# MCU089A_XDS110_MCU.net
KiCad netlist of a schematic drawn in Altium Designer
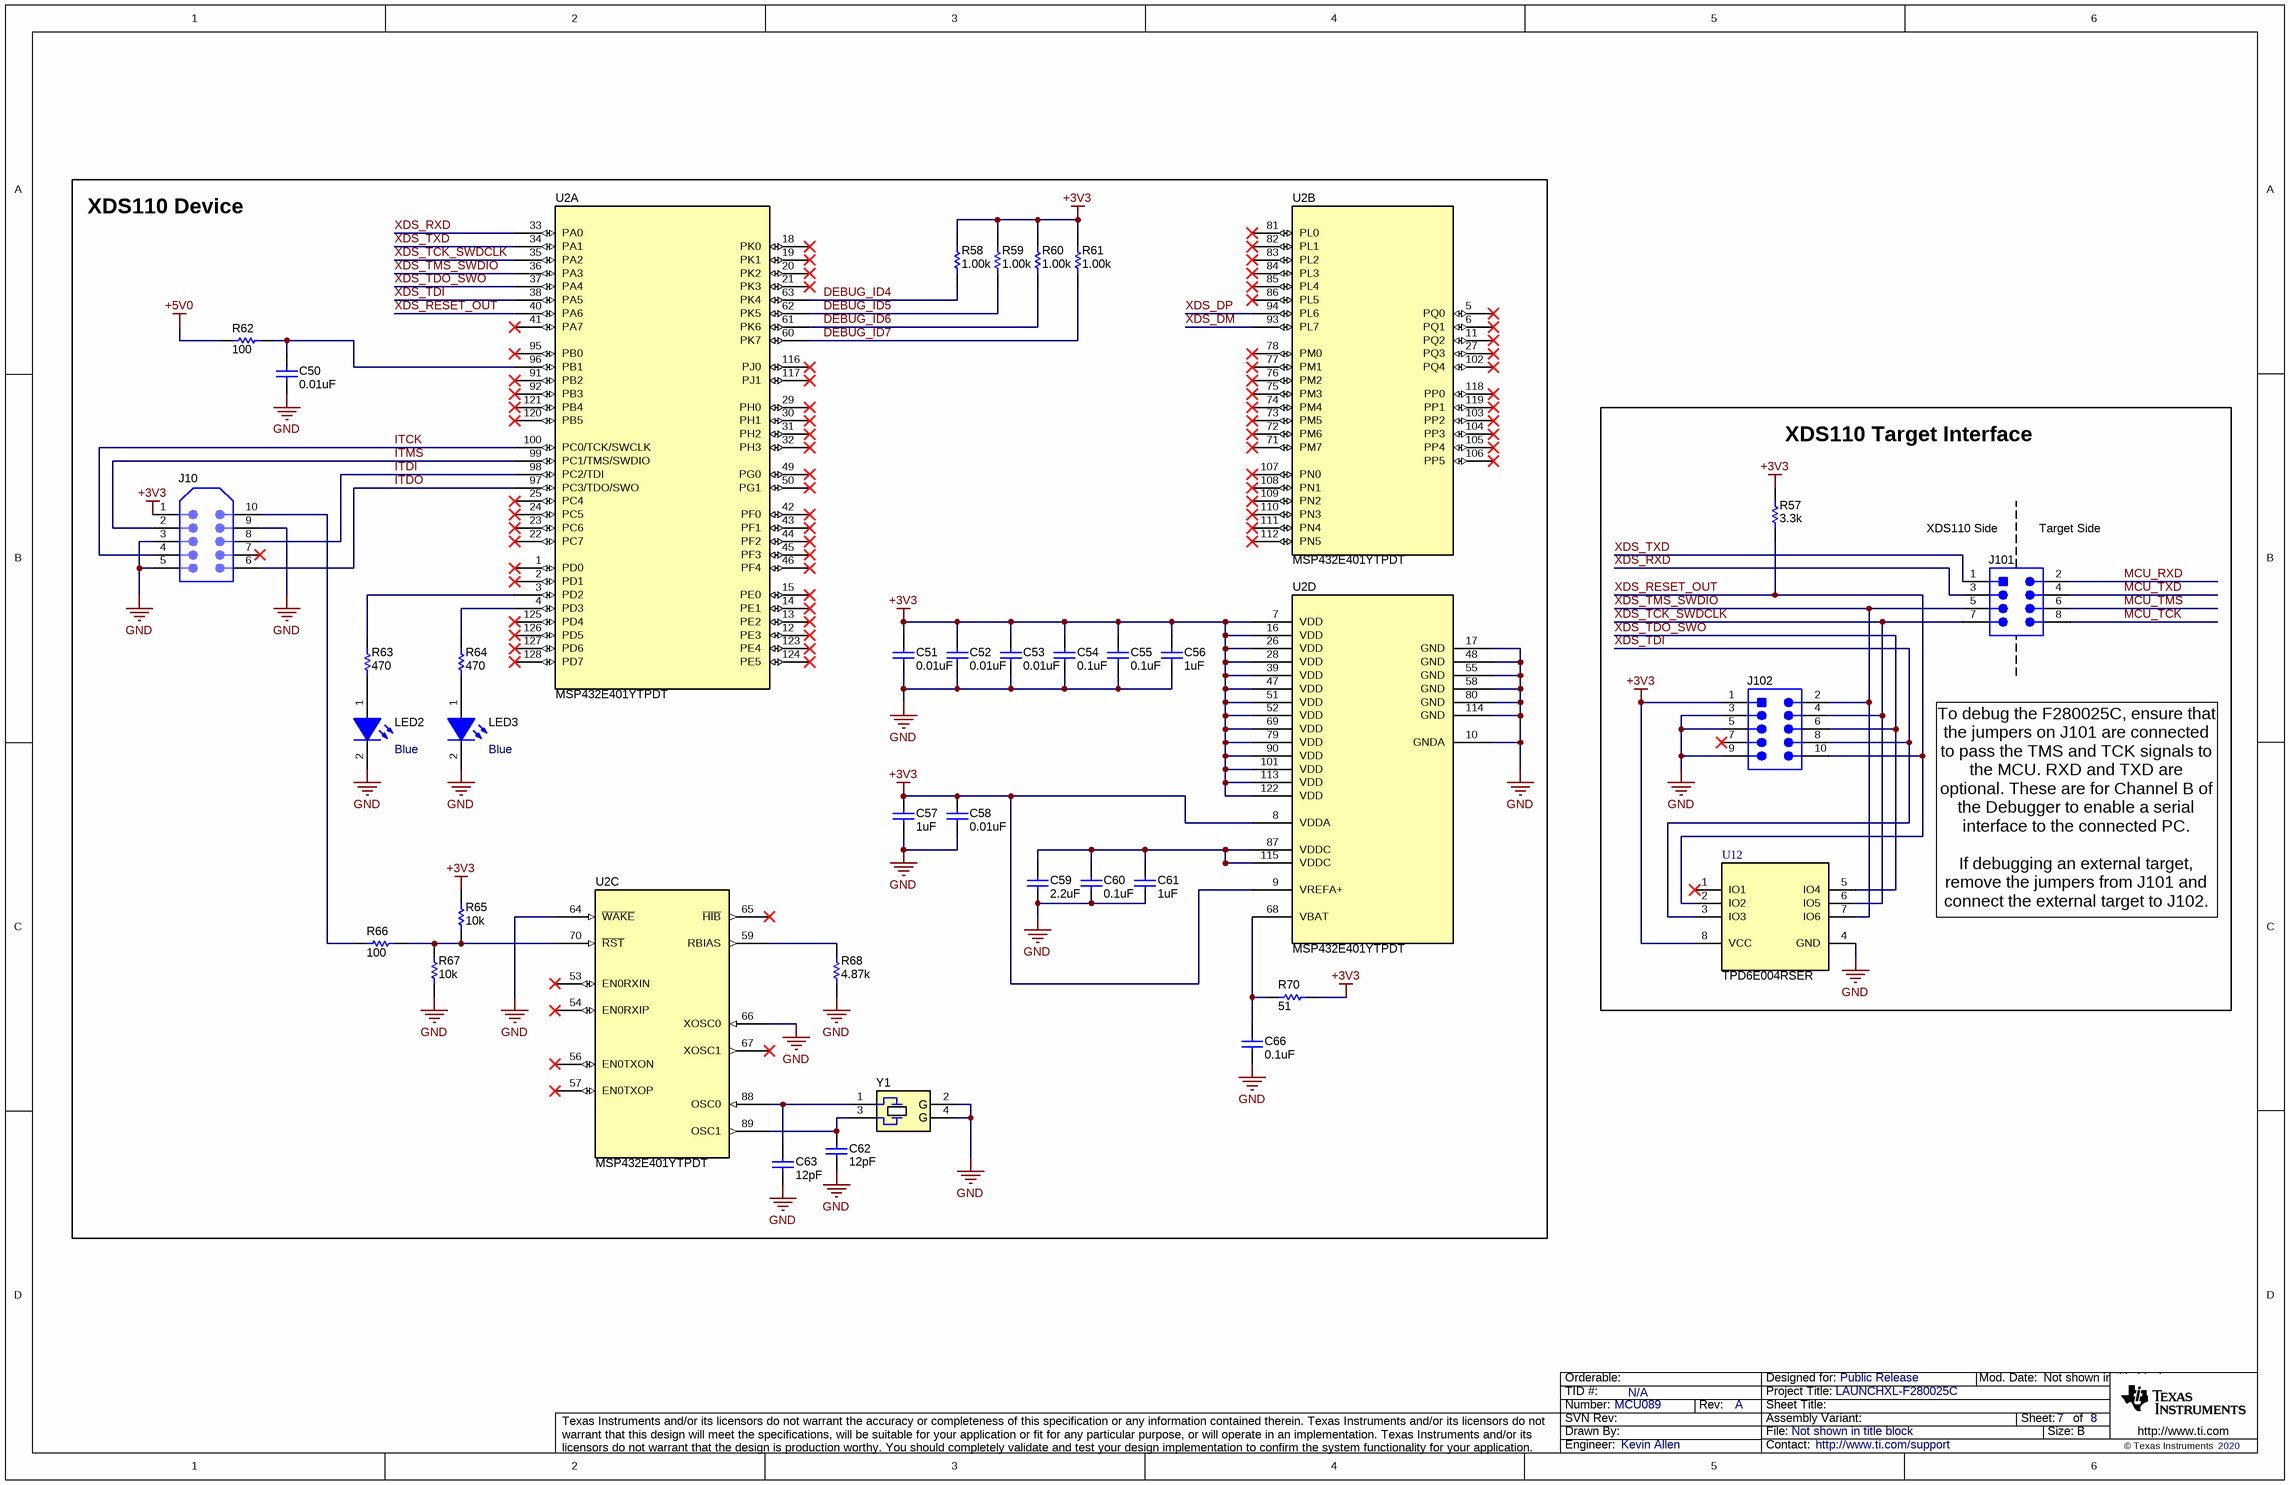
[diagram p0: MCU089A_XDS110_MCU.SchDoc]

(export (version "E")
  (design (tool "Eeschema 10.0.6"))
  (components
    (comp (ref "C50")
      (value "GRM155R71E103KA01D")
      (footprint "0402")
      (description "CAP, CERM, 0.01 uF, 25 V, +/- 10%, X7R, 0402")
      (fields
        (field (name "VALUEDISPLAYED") "0.01uF")
        (field (name "MANUFACTURER") "MuRata")
        (field (name "PUBLISHER") "Texas Instruments")
      )
      (libsource (lib "Altium Vault - TI") (part "Capacitor"))
    )
    (comp (ref "C51")
      (value "GRM155R71E103KA01D")
      (footprint "0402")
      (description "CAP, CERM, 0.01 uF, 25 V, +/- 10%, X7R, 0402")
      (fields
        (field (name "VALUEDISPLAYED") "0.01uF")
        (field (name "MANUFACTURER") "MuRata")
        (field (name "PUBLISHER") "Texas Instruments")
      )
      (libsource (lib "Altium Vault - TI") (part "Capacitor"))
    )
    (comp (ref "C52")
      (value "GRM155R71E103KA01D")
      (footprint "0402")
      (description "CAP, CERM, 0.01 uF, 25 V, +/- 10%, X7R, 0402")
      (fields
        (field (name "VALUEDISPLAYED") "0.01uF")
        (field (name "MANUFACTURER") "MuRata")
        (field (name "PUBLISHER") "Texas Instruments")
      )
      (libsource (lib "Altium Vault - TI") (part "Capacitor"))
    )
    (comp (ref "C53")
      (value "GRM155R71E103KA01D")
      (footprint "0402")
      (description "CAP, CERM, 0.01 uF, 25 V, +/- 10%, X7R, 0402")
      (fields
        (field (name "VALUEDISPLAYED") "0.01uF")
        (field (name "MANUFACTURER") "MuRata")
        (field (name "PUBLISHER") "Texas Instruments")
      )
      (libsource (lib "Altium Vault - TI") (part "Capacitor"))
    )
    (comp (ref "C54")
      (value "GRM155R70J104KA01D")
      (footprint "0402")
      (description "CAP, CERM, 0.1 uF, 6.3 V, +/- 10%, X7R, 0402")
      (fields
        (field (name "VALUEDISPLAYED") "0.1uF")
        (field (name "MANUFACTURER") "MuRata")
        (field (name "PUBLISHER") "Texas Instruments")
      )
      (libsource (lib "Altium Vault - TI") (part "Capacitor"))
    )
    (comp (ref "C55")
      (value "GRM155R70J104KA01D")
      (footprint "0402")
      (description "CAP, CERM, 0.1 uF, 6.3 V, +/- 10%, X7R, 0402")
      (fields
        (field (name "VALUEDISPLAYED") "0.1uF")
        (field (name "MANUFACTURER") "MuRata")
        (field (name "PUBLISHER") "Texas Instruments")
      )
      (libsource (lib "Altium Vault - TI") (part "Capacitor"))
    )
    (comp (ref "C56")
      (value "885012105012")
      (footprint "0402")
      (description "CAP, CERM, 1 uF, 10 V,+/- 20%, X5R, 0402")
      (fields
        (field (name "VALUEDISPLAYED") "1uF")
        (field (name "MANUFACTURER") "Wurth Elektronik")
        (field (name "PUBLISHER") "Texas Instruments")
      )
      (libsource (lib "Altium Vault - TI") (part "Capacitor"))
    )
    (comp (ref "C57")
      (value "885012105012")
      (footprint "0402")
      (description "CAP, CERM, 1 uF, 10 V,+/- 20%, X5R, 0402")
      (fields
        (field (name "VALUEDISPLAYED") "1uF")
        (field (name "MANUFACTURER") "Wurth Elektronik")
        (field (name "PUBLISHER") "Texas Instruments")
      )
      (libsource (lib "Altium Vault - TI") (part "Capacitor"))
    )
    (comp (ref "C58")
      (value "GRM155R71E103KA01D")
      (footprint "0402")
      (description "CAP, CERM, 0.01 uF, 25 V, +/- 10%, X7R, 0402")
      (fields
        (field (name "VALUEDISPLAYED") "0.01uF")
        (field (name "MANUFACTURER") "MuRata")
        (field (name "PUBLISHER") "Texas Instruments")
      )
      (libsource (lib "Altium Vault - TI") (part "Capacitor"))
    )
    (comp (ref "C59")
      (value "GRM155R60J225KE95D")
      (footprint "0402")
      (description "CAP, CERM, 2.2 uF, 6.3 V, +/- 10%, X5R, 0402")
      (fields
        (field (name "VALUEDISPLAYED") "2.2uF")
        (field (name "MANUFACTURER") "MuRata")
        (field (name "PUBLISHER") "Texas Instruments")
      )
      (libsource (lib "Altium Vault - TI") (part "Capacitor"))
    )
    (comp (ref "C60")
      (value "GRM155R70J104KA01D")
      (footprint "0402")
      (description "CAP, CERM, 0.1 uF, 6.3 V, +/- 10%, X7R, 0402")
      (fields
        (field (name "VALUEDISPLAYED") "0.1uF")
        (field (name "MANUFACTURER") "MuRata")
        (field (name "PUBLISHER") "Texas Instruments")
      )
      (libsource (lib "Altium Vault - TI") (part "Capacitor"))
    )
    (comp (ref "C61")
      (value "885012105012")
      (footprint "0402")
      (description "CAP, CERM, 1 uF, 10 V,+/- 20%, X5R, 0402")
      (fields
        (field (name "VALUEDISPLAYED") "1uF")
        (field (name "MANUFACTURER") "Wurth Elektronik")
        (field (name "PUBLISHER") "Texas Instruments")
      )
      (libsource (lib "Altium Vault - TI") (part "Capacitor"))
    )
    (comp (ref "C62")
      (value "C0402C120J3GACAUTO")
      (footprint "0402")
      (description "CAP, CERM, 12 pF, 25 V, +/- 5%, C0G/NP0, AEC-Q200 Grade 1, 0402")
      (fields
        (field (name "MANUFACTURER") "Kemet")
        (field (name "VALUEDISPLAYED") "12pF")
        (field (name "PUBLISHER") "Texas Instruments")
      )
      (libsource (lib "Altium Vault - TI") (part "Capacitor"))
    )
    (comp (ref "C63")
      (value "C0402C120J3GACAUTO")
      (footprint "0402")
      (description "CAP, CERM, 12 pF, 25 V, +/- 5%, C0G/NP0, AEC-Q200 Grade 1, 0402")
      (fields
        (field (name "MANUFACTURER") "Kemet")
        (field (name "VALUEDISPLAYED") "12pF")
        (field (name "PUBLISHER") "Texas Instruments")
      )
      (libsource (lib "Altium Vault - TI") (part "Capacitor"))
    )
    (comp (ref "C66")
      (value "GRM155R70J104KA01D")
      (footprint "0402")
      (description "CAP, CERM, 0.1 uF, 6.3 V, +/- 10%, X7R, 0402")
      (fields
        (field (name "VALUEDISPLAYED") "0.1uF")
        (field (name "MANUFACTURER") "MuRata")
        (field (name "PUBLISHER") "Texas Instruments")
      )
      (libsource (lib "Altium Vault - TI") (part "Capacitor"))
    )
    (comp (ref "J10")
      (value "TC2050-IDC-NL-FP")
      (footprint "Tag_TC2050-NL")
      (description "Footprint for Tag-Connect TC2050 No-Legs cables")
      (fields (field (name "MANUFACTURER") "Tag-Connect") (field (name "PUBLISHER") "Texas Instruments"))
      (libsource (lib "Altium Vault - TI") (part "CMP-0075101-1"))
    )
    (comp (ref "J101")
      (value "TSW-104-07-G-D")
      (footprint "TSW-104-07-G-D")
      (description "Header, 100mil, 4x2, Gold, TH")
      (fields (field (name "MANUFACTURER") "Samtec"))
      (libsource (lib "Altium Vault - TI") (part "Header_4x2"))
    )
    (comp (ref "J102")
      (value "FTSH-105-01-F-DV-K")
      (footprint "Samtec_FTSH-105-01-x-DV-K")
      (description "Header (Shrouded), 1.27mm, 5x2, Gold, SMT")
      (fields (field (name "MANUFACTURER") "Samtec"))
      (libsource (lib "Altium Vault - TI") (part "Header_5x2"))
    )
    (comp (ref "LED2")
      (value "Blue")
      (footprint "LTST-C170TBKT_Blue")
      (description "LED, Blue, SMD")
      (fields (field (name "PARTNUMBER") "LTST-C170TBKT") (field (name "MANUFACTURER") "Lite-On"))
      (libsource (lib "Altium Vault - TI") (part "LED"))
    )
    (comp (ref "LED3")
      (value "Blue")
      (footprint "LTST-C170TBKT_Blue")
      (description "LED, Blue, SMD")
      (fields (field (name "PARTNUMBER") "LTST-C170TBKT") (field (name "MANUFACTURER") "Lite-On"))
      (libsource (lib "Altium Vault - TI") (part "LED"))
    )
    (comp (ref "R57")
      (value "CRCW04023K30JNED")
      (footprint "0402")
      (description "RES, 3.3 k, 5%, 0.063 W, AEC-Q200 Grade 0, 0402")
      (fields (field (name "VALUEDISPLAYED") "3.3k") (field (name "MANUFACTURER") "Vishay-Dale"))
      (libsource (lib "Altium Vault - TI") (part "Resistor"))
    )
    (comp (ref "R58")
      (value "CRCW04021K00FKED")
      (footprint "0402")
      (description "RES, 1.00 k, 1%, 0.063 W, AEC-Q200 Grade 0, 0402")
      (fields (field (name "MANUFACTURER") "Vishay-Dale") (field (name "VALUEDISPLAYED") "1.00k"))
      (libsource (lib "Altium Vault - TI") (part "Resistor"))
    )
    (comp (ref "R59")
      (value "CRCW04021K00FKED")
      (footprint "0402")
      (description "RES, 1.00 k, 1%, 0.063 W, AEC-Q200 Grade 0, 0402")
      (fields (field (name "MANUFACTURER") "Vishay-Dale") (field (name "VALUEDISPLAYED") "1.00k"))
      (libsource (lib "Altium Vault - TI") (part "Resistor"))
    )
    (comp (ref "R60")
      (value "CRCW04021K00FKED")
      (footprint "0402")
      (description "RES, 1.00 k, 1%, 0.063 W, AEC-Q200 Grade 0, 0402")
      (fields (field (name "MANUFACTURER") "Vishay-Dale") (field (name "VALUEDISPLAYED") "1.00k"))
      (libsource (lib "Altium Vault - TI") (part "Resistor"))
    )
    (comp (ref "R61")
      (value "CRCW04021K00FKED")
      (footprint "0402")
      (description "RES, 1.00 k, 1%, 0.063 W, AEC-Q200 Grade 0, 0402")
      (fields (field (name "MANUFACTURER") "Vishay-Dale") (field (name "VALUEDISPLAYED") "1.00k"))
      (libsource (lib "Altium Vault - TI") (part "Resistor"))
    )
    (comp (ref "R62")
      (value "CRCW0402100RJNED")
      (footprint "0402")
      (description "RES, 100, 5%, 0.063 W, AEC-Q200 Grade 0, 0402")
      (fields (field (name "VALUEDISPLAYED") "100") (field (name "MANUFACTURER") "Vishay-Dale"))
      (libsource (lib "Altium Vault - TI") (part "Resistor"))
    )
    (comp (ref "R63")
      (value "ERJ-2RKF4700X")
      (footprint "0402")
      (description "RES, 470, 1%, 0.1 W, AEC-Q200 Grade 0, 0402")
      (fields
        (field (name "VALUEDISPLAYED") "470")
        (field (name "MANUFACTURER") "Panasonic")
        (field (name "PUBLISHER") "Texas Instruments")
      )
      (libsource (lib "Altium Vault - TI") (part "Resistor"))
    )
    (comp (ref "R64")
      (value "ERJ-2RKF4700X")
      (footprint "0402")
      (description "RES, 470, 1%, 0.1 W, AEC-Q200 Grade 0, 0402")
      (fields
        (field (name "VALUEDISPLAYED") "470")
        (field (name "MANUFACTURER") "Panasonic")
        (field (name "PUBLISHER") "Texas Instruments")
      )
      (libsource (lib "Altium Vault - TI") (part "Resistor"))
    )
    (comp (ref "R65")
      (value "CRCW040210K0JNED")
      (footprint "0402")
      (description "RES, 10 k, 5%, 0.063 W, AEC-Q200 Grade 0, 0402")
      (fields (field (name "VALUEDISPLAYED") "10k") (field (name "MANUFACTURER") "Vishay-Dale"))
      (libsource (lib "Altium Vault - TI") (part "Resistor"))
    )
    (comp (ref "R66")
      (value "CRCW0402100RJNED")
      (footprint "0402")
      (description "RES, 100, 5%, 0.063 W, AEC-Q200 Grade 0, 0402")
      (fields (field (name "VALUEDISPLAYED") "100") (field (name "MANUFACTURER") "Vishay-Dale"))
      (libsource (lib "Altium Vault - TI") (part "Resistor"))
    )
    (comp (ref "R67")
      (value "CRCW040210K0JNED")
      (footprint "0402")
      (description "RES, 10 k, 5%, 0.063 W, AEC-Q200 Grade 0, 0402")
      (fields (field (name "VALUEDISPLAYED") "10k") (field (name "MANUFACTURER") "Vishay-Dale"))
      (libsource (lib "Altium Vault - TI") (part "Resistor"))
    )
    (comp (ref "R68")
      (value "CRCW04024K87FKED")
      (footprint "0402")
      (description "RES, 4.87 k, 1%, 0.063 W, AEC-Q200 Grade 0, 0402")
      (fields (field (name "VALUEDISPLAYED") "4.87k") (field (name "MANUFACTURER") "Vishay-Dale"))
      (libsource (lib "Altium Vault - TI") (part "Resistor"))
    )
    (comp (ref "R70")
      (value "CRCW040251R0JNED")
      (footprint "0402")
      (description "RES, 51, 5%, 0.063 W, AEC-Q200 Grade 0, 0402")
      (fields (field (name "VALUEDISPLAYED") "51") (field (name "MANUFACTURER") "Vishay-Dale"))
      (libsource (lib "Altium Vault - TI") (part "Resistor"))
    )
    (comp (ref "U2")
      (value "MSP432E401YTPDT")
      (footprint "PDT0128A")
      (description "MSP432E401YTPDT, PDT0128A (TQFP-128)")
      (fields
        (field (name "ALTERNATE PARTNUMBER") "MSP432E401YTPDTR")
        (field (name "MANUFACTURER") "Texas Instruments")
        (field (name "PARTNUMBER") "MSP432E401YTPDT")
      )
      (libsource (lib "Altium Vault - TI") (part "MSP432E401YTPDT"))
    )
    (comp (ref "U12")
      (value "TPD6E004RSER")
      (footprint "RSE0008A")
      (fields (field (name "MANUFACTURER") "Texas Instruments") (field (name "PARTNUMBER") "TPD6E004RSER"))
      (libsource (lib "Altium Vault - TI") (part "TI-TPD6E004-UQFN_RSE-8"))
    )
    (comp (ref "Y1")
      (value "NX3225GA-16.000M-STD-CRG-1")
      (footprint "NDK_NX3225GA")
      (description "Crystal, 16 MHz, 8pF, SMD")
      (fields (field (name "MANUFACTURER") "NDK"))
      (libsource (lib "Altium Vault - TI") (part "XTAL_4P_13_G24"))
    )
  )
  (nets
    (net (code "1") (name "+3V3") (class "Default")
      (node (ref "C51") (pin "1") (pinfunction "1_1") (pintype "passive"))
      (node (ref "C52") (pin "1") (pinfunction "1_1") (pintype "passive"))
      (node (ref "C53") (pin "1") (pinfunction "1_1") (pintype "passive"))
      (node (ref "C54") (pin "1") (pinfunction "1_1") (pintype "passive"))
      (node (ref "C55") (pin "1") (pinfunction "1_1") (pintype "passive"))
      (node (ref "C56") (pin "1") (pinfunction "1_1") (pintype "passive"))
      (node (ref "C57") (pin "1") (pinfunction "1_1") (pintype "passive"))
      (node (ref "C58") (pin "1") (pinfunction "1_1") (pintype "passive"))
      (node (ref "J10") (pin "1") (pinfunction "1_1") (pintype "passive"))
      (node (ref "J102") (pin "1") (pinfunction "1_1") (pintype "passive"))
      (node (ref "R57") (pin "2") (pinfunction "2_2") (pintype "passive"))
      (node (ref "R58") (pin "2") (pinfunction "2_2") (pintype "passive"))
      (node (ref "R59") (pin "2") (pinfunction "2_2") (pintype "passive"))
      (node (ref "R60") (pin "2") (pinfunction "2_2") (pintype "passive"))
      (node (ref "R61") (pin "2") (pinfunction "2_2") (pintype "passive"))
      (node (ref "R65") (pin "2") (pinfunction "2_2") (pintype "passive"))
      (node (ref "R70") (pin "2") (pinfunction "2_2") (pintype "passive"))
      (node (ref "U12") (pin "8") (pinfunction "VCC_8") (pintype "power_in"))
      (node (ref "U2") (pin "101") (pinfunction "VDD_101") (pintype "power_in"))
      (node (ref "U2") (pin "113") (pinfunction "VDD_113") (pintype "power_in"))
      (node (ref "U2") (pin "122") (pinfunction "VDD_122") (pintype "power_in"))
      (node (ref "U2") (pin "16") (pinfunction "VDD_16") (pintype "power_in"))
      (node (ref "U2") (pin "26") (pinfunction "VDD_26") (pintype "power_in"))
      (node (ref "U2") (pin "28") (pinfunction "VDD_28") (pintype "power_in"))
      (node (ref "U2") (pin "39") (pinfunction "VDD_39") (pintype "power_in"))
      (node (ref "U2") (pin "47") (pinfunction "VDD_47") (pintype "power_in"))
      (node (ref "U2") (pin "51") (pinfunction "VDD_51") (pintype "power_in"))
      (node (ref "U2") (pin "52") (pinfunction "VDD_52") (pintype "power_in"))
      (node (ref "U2") (pin "69") (pinfunction "VDD_69") (pintype "power_in"))
      (node (ref "U2") (pin "7") (pinfunction "VDD_7") (pintype "power_in"))
      (node (ref "U2") (pin "79") (pinfunction "VDD_79") (pintype "power_in"))
      (node (ref "U2") (pin "8") (pinfunction "VDDA_8") (pintype "power_in"))
      (node (ref "U2") (pin "9") (pinfunction "VREFA+_9") (pintype "power_in"))
      (node (ref "U2") (pin "90") (pinfunction "VDD_90") (pintype "power_in"))
    )
    (net (code "2") (name "+5V0") (class "Default")
      (node (ref "R62") (pin "1") (pinfunction "1_1") (pintype "passive"))
    )
    (net (code "3") (name "/DEBUG_ID4") (class "Default")
      (node (ref "R58") (pin "1") (pinfunction "1_1") (pintype "passive"))
      (node (ref "U2") (pin "63") (pinfunction "PK4_63") (pintype "bidirectional"))
    )
    (net (code "4") (name "/DEBUG_ID5") (class "Default")
      (node (ref "R59") (pin "1") (pinfunction "1_1") (pintype "passive"))
      (node (ref "U2") (pin "62") (pinfunction "PK5_62") (pintype "bidirectional"))
    )
    (net (code "5") (name "/DEBUG_ID6") (class "Default")
      (node (ref "R60") (pin "1") (pinfunction "1_1") (pintype "passive"))
      (node (ref "U2") (pin "61") (pinfunction "PK6_61") (pintype "bidirectional"))
    )
    (net (code "6") (name "/DEBUG_ID7") (class "Default")
      (node (ref "R61") (pin "1") (pinfunction "1_1") (pintype "passive"))
      (node (ref "U2") (pin "60") (pinfunction "PK7_60") (pintype "bidirectional"))
    )
    (net (code "7") (name "/ITCK") (class "Default")
      (node (ref "J10") (pin "4") (pinfunction "4_4") (pintype "passive"))
      (node (ref "U2") (pin "100") (pinfunction "PC0/TCK/SWCLK_100") (pintype "bidirectional"))
    )
    (net (code "8") (name "/ITDI") (class "Default")
      (node (ref "J10") (pin "8") (pinfunction "8_8") (pintype "passive"))
      (node (ref "U2") (pin "98") (pinfunction "PC2/TDI_98") (pintype "bidirectional"))
    )
    (net (code "9") (name "/ITDO") (class "Default")
      (node (ref "J10") (pin "6") (pinfunction "6_6") (pintype "passive"))
      (node (ref "U2") (pin "97") (pinfunction "PC3/TDO/SWO_97") (pintype "bidirectional"))
    )
    (net (code "10") (name "/ITMS") (class "Default")
      (node (ref "J10") (pin "2") (pinfunction "2_2") (pintype "passive"))
      (node (ref "U2") (pin "99") (pinfunction "PC1/TMS/SWDIO_99") (pintype "bidirectional"))
    )
    (net (code "11") (name "/MCU_RXD") (class "Default")
      (node (ref "J101") (pin "2") (pinfunction "2_2") (pintype "passive"))
    )
    (net (code "12") (name "/MCU_TCK") (class "Default")
      (node (ref "J101") (pin "8") (pinfunction "8_8") (pintype "passive"))
    )
    (net (code "13") (name "/MCU_TMS") (class "Default")
      (node (ref "J101") (pin "6") (pinfunction "6_6") (pintype "passive"))
    )
    (net (code "14") (name "/MCU_TXD") (class "Default")
      (node (ref "J101") (pin "4") (pinfunction "4_4") (pintype "passive"))
    )
    (net (code "15") (name "/XDS_DM") (class "Default")
      (node (ref "U2") (pin "93") (pinfunction "PL7_93") (pintype "bidirectional"))
    )
    (net (code "16") (name "/XDS_DP") (class "Default")
      (node (ref "U2") (pin "94") (pinfunction "PL6_94") (pintype "bidirectional"))
    )
    (net (code "17") (name "/XDS_RESET_OUT") (class "Default")
      (node (ref "J102") (pin "10") (pinfunction "10_10") (pintype "passive"))
      (node (ref "R57") (pin "1") (pinfunction "1_1") (pintype "passive"))
      (node (ref "U12") (pin "2") (pinfunction "IO2_2") (pintype "passive"))
      (node (ref "U2") (pin "40") (pinfunction "PA6_40") (pintype "bidirectional"))
    )
    (net (code "18") (name "/XDS_RXD") (class "Default")
      (node (ref "J101") (pin "3") (pinfunction "3_3") (pintype "passive"))
      (node (ref "U2") (pin "33") (pinfunction "PA0_33") (pintype "bidirectional"))
    )
    (net (code "19") (name "/XDS_TCK_SWDCLK") (class "Default")
      (node (ref "J101") (pin "7") (pinfunction "7_7") (pintype "passive"))
      (node (ref "J102") (pin "4") (pinfunction "4_4") (pintype "passive"))
      (node (ref "U12") (pin "6") (pinfunction "IO5_6") (pintype "passive"))
      (node (ref "U2") (pin "35") (pinfunction "PA2_35") (pintype "bidirectional"))
    )
    (net (code "20") (name "/XDS_TDI") (class "Default")
      (node (ref "J102") (pin "8") (pinfunction "8_8") (pintype "passive"))
      (node (ref "U12") (pin "3") (pinfunction "IO3_3") (pintype "passive"))
      (node (ref "U2") (pin "38") (pinfunction "PA5_38") (pintype "bidirectional"))
    )
    (net (code "21") (name "/XDS_TDO_SWO") (class "Default")
      (node (ref "J102") (pin "6") (pinfunction "6_6") (pintype "passive"))
      (node (ref "U12") (pin "5") (pinfunction "IO4_5") (pintype "passive"))
      (node (ref "U2") (pin "37") (pinfunction "PA4_37") (pintype "bidirectional"))
    )
    (net (code "22") (name "/XDS_TMS_SWDIO") (class "Default")
      (node (ref "J101") (pin "5") (pinfunction "5_5") (pintype "passive"))
      (node (ref "J102") (pin "2") (pinfunction "2_2") (pintype "passive"))
      (node (ref "U12") (pin "7") (pinfunction "IO6_7") (pintype "passive"))
      (node (ref "U2") (pin "36") (pinfunction "PA3_36") (pintype "bidirectional"))
    )
    (net (code "23") (name "/XDS_TXD") (class "Default")
      (node (ref "J101") (pin "1") (pinfunction "1_1") (pintype "passive"))
      (node (ref "U2") (pin "34") (pinfunction "PA1_34") (pintype "bidirectional"))
    )
    (net (code "24") (name "GND") (class "Default")
      (node (ref "C50") (pin "2") (pinfunction "2_2") (pintype "passive"))
      (node (ref "C51") (pin "2") (pinfunction "2_2") (pintype "passive"))
      (node (ref "C52") (pin "2") (pinfunction "2_2") (pintype "passive"))
      (node (ref "C53") (pin "2") (pinfunction "2_2") (pintype "passive"))
      (node (ref "C54") (pin "2") (pinfunction "2_2") (pintype "passive"))
      (node (ref "C55") (pin "2") (pinfunction "2_2") (pintype "passive"))
      (node (ref "C56") (pin "2") (pinfunction "2_2") (pintype "passive"))
      (node (ref "C57") (pin "2") (pinfunction "2_2") (pintype "passive"))
      (node (ref "C58") (pin "2") (pinfunction "2_2") (pintype "passive"))
      (node (ref "C59") (pin "2") (pinfunction "2_2") (pintype "passive"))
      (node (ref "C60") (pin "2") (pinfunction "2_2") (pintype "passive"))
      (node (ref "C61") (pin "2") (pinfunction "2_2") (pintype "passive"))
      (node (ref "C62") (pin "2") (pinfunction "2_2") (pintype "passive"))
      (node (ref "C63") (pin "2") (pinfunction "2_2") (pintype "passive"))
      (node (ref "C66") (pin "2") (pinfunction "2_2") (pintype "passive"))
      (node (ref "J10") (pin "3") (pinfunction "3_3") (pintype "passive"))
      (node (ref "J10") (pin "5") (pinfunction "5_5") (pintype "passive"))
      (node (ref "J10") (pin "9") (pinfunction "9_9") (pintype "passive"))
      (node (ref "J102") (pin "3") (pinfunction "3_3") (pintype "passive"))
      (node (ref "J102") (pin "5") (pinfunction "5_5") (pintype "passive"))
      (node (ref "J102") (pin "9") (pinfunction "9_9") (pintype "passive"))
      (node (ref "LED2") (pin "2") (pinfunction "K_2") (pintype "passive"))
      (node (ref "LED3") (pin "2") (pinfunction "K_2") (pintype "passive"))
      (node (ref "R67") (pin "1") (pinfunction "1_1") (pintype "passive"))
      (node (ref "R68") (pin "1") (pinfunction "1_1") (pintype "passive"))
      (node (ref "U12") (pin "4") (pinfunction "GND_4") (pintype "power_in"))
      (node (ref "U2") (pin "10") (pinfunction "GNDA_10") (pintype "power_in"))
      (node (ref "U2") (pin "114") (pinfunction "GND_114") (pintype "power_in"))
      (node (ref "U2") (pin "17") (pinfunction "GND_17") (pintype "power_in"))
      (node (ref "U2") (pin "48") (pinfunction "GND_48") (pintype "power_in"))
      (node (ref "U2") (pin "55") (pinfunction "GND_55") (pintype "power_in"))
      (node (ref "U2") (pin "58") (pinfunction "GND_58") (pintype "power_in"))
      (node (ref "U2") (pin "64") (pinfunction "WAKE_64") (pintype "input"))
      (node (ref "U2") (pin "66") (pinfunction "XOSC0_66") (pintype "input"))
      (node (ref "U2") (pin "80") (pinfunction "GND_80") (pintype "power_in"))
      (node (ref "Y1") (pin "2") (pinfunction "GND_2") (pintype "power_in"))
      (node (ref "Y1") (pin "4") (pinfunction "GND_4") (pintype "power_in"))
    )
    (net (code "25") (name "Net-(C59-Pad1)") (class "Default")
      (node (ref "C59") (pin "1") (pinfunction "1_1") (pintype "passive"))
      (node (ref "C60") (pin "1") (pinfunction "1_1") (pintype "passive"))
      (node (ref "C61") (pin "1") (pinfunction "1_1") (pintype "passive"))
      (node (ref "U2") (pin "115") (pinfunction "VDDC_115") (pintype "power_in"))
      (node (ref "U2") (pin "87") (pinfunction "VDDC_87") (pintype "power_in"))
    )
    (net (code "26") (name "Net-(J10-Pad10)") (class "Default")
      (node (ref "J10") (pin "10") (pinfunction "10_10") (pintype "passive"))
      (node (ref "R66") (pin "1") (pinfunction "1_1") (pintype "passive"))
    )
    (net (code "27") (name "Net-(LED2-A)") (class "Default")
      (node (ref "LED2") (pin "1") (pinfunction "A_1") (pintype "passive"))
      (node (ref "R63") (pin "1") (pinfunction "1_1") (pintype "passive"))
    )
    (net (code "28") (name "Net-(LED3-A)") (class "Default")
      (node (ref "LED3") (pin "1") (pinfunction "A_1") (pintype "passive"))
      (node (ref "R64") (pin "1") (pinfunction "1_1") (pintype "passive"))
    )
    (net (code "29") (name "Net-(U2A-PB1)") (class "Default")
      (node (ref "C50") (pin "1") (pinfunction "1_1") (pintype "passive"))
      (node (ref "R62") (pin "2") (pinfunction "2_2") (pintype "passive"))
      (node (ref "U2") (pin "96") (pinfunction "PB1_96") (pintype "bidirectional"))
    )
    (net (code "30") (name "Net-(U2A-PD2)") (class "Default")
      (node (ref "R63") (pin "2") (pinfunction "2_2") (pintype "passive"))
      (node (ref "U2") (pin "3") (pinfunction "PD2_3") (pintype "bidirectional"))
    )
    (net (code "31") (name "Net-(U2A-PD3)") (class "Default")
      (node (ref "R64") (pin "2") (pinfunction "2_2") (pintype "passive"))
      (node (ref "U2") (pin "4") (pinfunction "PD3_4") (pintype "bidirectional"))
    )
    (net (code "32") (name "Net-(U2C-OSC0)") (class "Default")
      (node (ref "C63") (pin "1") (pinfunction "1_1") (pintype "passive"))
      (node (ref "U2") (pin "88") (pinfunction "OSC0_88") (pintype "input"))
      (node (ref "Y1") (pin "1") (pinfunction "1_1") (pintype "passive"))
    )
    (net (code "33") (name "Net-(U2C-OSC1)") (class "Default")
      (node (ref "C62") (pin "1") (pinfunction "1_1") (pintype "passive"))
      (node (ref "U2") (pin "89") (pinfunction "OSC1_89") (pintype "output"))
      (node (ref "Y1") (pin "3") (pinfunction "3_3") (pintype "passive"))
    )
    (net (code "34") (name "Net-(U2C-RBIAS)") (class "Default")
      (node (ref "R68") (pin "2") (pinfunction "2_2") (pintype "passive"))
      (node (ref "U2") (pin "59") (pinfunction "RBIAS_59") (pintype "output"))
    )
    (net (code "35") (name "Net-(U2C-RST)") (class "Default")
      (node (ref "R65") (pin "1") (pinfunction "1_1") (pintype "passive"))
      (node (ref "R66") (pin "2") (pinfunction "2_2") (pintype "passive"))
      (node (ref "R67") (pin "2") (pinfunction "2_2") (pintype "passive"))
      (node (ref "U2") (pin "70") (pinfunction "RST_70") (pintype "input"))
    )
    (net (code "36") (name "Net-(U2D-VBAT)") (class "Default")
      (node (ref "C66") (pin "1") (pinfunction "1_1") (pintype "passive"))
      (node (ref "R70") (pin "1") (pinfunction "1_1") (pintype "passive"))
      (node (ref "U2") (pin "68") (pinfunction "VBAT_68") (pintype "power_in"))
    )
    (net (code "37") (name "unconnected-(J10-Pad7)") (class "Default")
      (node (ref "J10") (pin "7") (pinfunction "7_7") (pintype "passive+no_connect"))
    )
    (net (code "38") (name "unconnected-(J102-Pad7)") (class "Default")
      (node (ref "J102") (pin "7") (pinfunction "7_7") (pintype "passive+no_connect"))
    )
    (net (code "39") (name "unconnected-(U2A-PA7-Pad41)") (class "Default")
      (node (ref "U2") (pin "41") (pinfunction "PA7_41") (pintype "bidirectional+no_connect"))
    )
    (net (code "40") (name "unconnected-(U2A-PB0-Pad95)") (class "Default")
      (node (ref "U2") (pin "95") (pinfunction "PB0_95") (pintype "bidirectional+no_connect"))
    )
    (net (code "41") (name "unconnected-(U2A-PB2-Pad91)") (class "Default")
      (node (ref "U2") (pin "91") (pinfunction "PB2_91") (pintype "bidirectional+no_connect"))
    )
    (net (code "42") (name "unconnected-(U2A-PB3-Pad92)") (class "Default")
      (node (ref "U2") (pin "92") (pinfunction "PB3_92") (pintype "bidirectional+no_connect"))
    )
    (net (code "43") (name "unconnected-(U2A-PB4-Pad121)") (class "Default")
      (node (ref "U2") (pin "121") (pinfunction "PB4_121") (pintype "bidirectional+no_connect"))
    )
    (net (code "44") (name "unconnected-(U2A-PB5-Pad120)") (class "Default")
      (node (ref "U2") (pin "120") (pinfunction "PB5_120") (pintype "bidirectional+no_connect"))
    )
    (net (code "45") (name "unconnected-(U2A-PC4-Pad25)") (class "Default")
      (node (ref "U2") (pin "25") (pinfunction "PC4_25") (pintype "bidirectional+no_connect"))
    )
    (net (code "46") (name "unconnected-(U2A-PC5-Pad24)") (class "Default")
      (node (ref "U2") (pin "24") (pinfunction "PC5_24") (pintype "bidirectional+no_connect"))
    )
    (net (code "47") (name "unconnected-(U2A-PC6-Pad23)") (class "Default")
      (node (ref "U2") (pin "23") (pinfunction "PC6_23") (pintype "bidirectional+no_connect"))
    )
    (net (code "48") (name "unconnected-(U2A-PC7-Pad22)") (class "Default")
      (node (ref "U2") (pin "22") (pinfunction "PC7_22") (pintype "bidirectional+no_connect"))
    )
    (net (code "49") (name "unconnected-(U2A-PD0-Pad1)") (class "Default")
      (node (ref "U2") (pin "1") (pinfunction "PD0_1") (pintype "bidirectional+no_connect"))
    )
    (net (code "50") (name "unconnected-(U2A-PD1-Pad2)") (class "Default")
      (node (ref "U2") (pin "2") (pinfunction "PD1_2") (pintype "bidirectional+no_connect"))
    )
    (net (code "51") (name "unconnected-(U2A-PD4-Pad125)") (class "Default")
      (node (ref "U2") (pin "125") (pinfunction "PD4_125") (pintype "bidirectional+no_connect"))
    )
    (net (code "52") (name "unconnected-(U2A-PD5-Pad126)") (class "Default")
      (node (ref "U2") (pin "126") (pinfunction "PD5_126") (pintype "bidirectional+no_connect"))
    )
    (net (code "53") (name "unconnected-(U2A-PD6-Pad127)") (class "Default")
      (node (ref "U2") (pin "127") (pinfunction "PD6_127") (pintype "bidirectional+no_connect"))
    )
    (net (code "54") (name "unconnected-(U2A-PD7-Pad128)") (class "Default")
      (node (ref "U2") (pin "128") (pinfunction "PD7_128") (pintype "bidirectional+no_connect"))
    )
    (net (code "55") (name "unconnected-(U2A-PE0-Pad15)") (class "Default")
      (node (ref "U2") (pin "15") (pinfunction "PE0_15") (pintype "bidirectional+no_connect"))
    )
    (net (code "56") (name "unconnected-(U2A-PE1-Pad14)") (class "Default")
      (node (ref "U2") (pin "14") (pinfunction "PE1_14") (pintype "bidirectional+no_connect"))
    )
    (net (code "57") (name "unconnected-(U2A-PE2-Pad13)") (class "Default")
      (node (ref "U2") (pin "13") (pinfunction "PE2_13") (pintype "bidirectional+no_connect"))
    )
    (net (code "58") (name "unconnected-(U2A-PE3-Pad12)") (class "Default")
      (node (ref "U2") (pin "12") (pinfunction "PE3_12") (pintype "bidirectional+no_connect"))
    )
    (net (code "59") (name "unconnected-(U2A-PE4-Pad123)") (class "Default")
      (node (ref "U2") (pin "123") (pinfunction "PE4_123") (pintype "bidirectional+no_connect"))
    )
    (net (code "60") (name "unconnected-(U2A-PE5-Pad124)") (class "Default")
      (node (ref "U2") (pin "124") (pinfunction "PE5_124") (pintype "bidirectional+no_connect"))
    )
    (net (code "61") (name "unconnected-(U2A-PF0-Pad42)") (class "Default")
      (node (ref "U2") (pin "42") (pinfunction "PF0_42") (pintype "bidirectional+no_connect"))
    )
    (net (code "62") (name "unconnected-(U2A-PF1-Pad43)") (class "Default")
      (node (ref "U2") (pin "43") (pinfunction "PF1_43") (pintype "bidirectional+no_connect"))
    )
    (net (code "63") (name "unconnected-(U2A-PF2-Pad44)") (class "Default")
      (node (ref "U2") (pin "44") (pinfunction "PF2_44") (pintype "bidirectional+no_connect"))
    )
    (net (code "64") (name "unconnected-(U2A-PF3-Pad45)") (class "Default")
      (node (ref "U2") (pin "45") (pinfunction "PF3_45") (pintype "bidirectional+no_connect"))
    )
    (net (code "65") (name "unconnected-(U2A-PF4-Pad46)") (class "Default")
      (node (ref "U2") (pin "46") (pinfunction "PF4_46") (pintype "bidirectional+no_connect"))
    )
    (net (code "66") (name "unconnected-(U2A-PG0-Pad49)") (class "Default")
      (node (ref "U2") (pin "49") (pinfunction "PG0_49") (pintype "bidirectional+no_connect"))
    )
    (net (code "67") (name "unconnected-(U2A-PG1-Pad50)") (class "Default")
      (node (ref "U2") (pin "50") (pinfunction "PG1_50") (pintype "bidirectional+no_connect"))
    )
    (net (code "68") (name "unconnected-(U2A-PH0-Pad29)") (class "Default")
      (node (ref "U2") (pin "29") (pinfunction "PH0_29") (pintype "bidirectional+no_connect"))
    )
    (net (code "69") (name "unconnected-(U2A-PH1-Pad30)") (class "Default")
      (node (ref "U2") (pin "30") (pinfunction "PH1_30") (pintype "bidirectional+no_connect"))
    )
    (net (code "70") (name "unconnected-(U2A-PH2-Pad31)") (class "Default")
      (node (ref "U2") (pin "31") (pinfunction "PH2_31") (pintype "bidirectional+no_connect"))
    )
    (net (code "71") (name "unconnected-(U2A-PH3-Pad32)") (class "Default")
      (node (ref "U2") (pin "32") (pinfunction "PH3_32") (pintype "bidirectional+no_connect"))
    )
    (net (code "72") (name "unconnected-(U2A-PJ0-Pad116)") (class "Default")
      (node (ref "U2") (pin "116") (pinfunction "PJ0_116") (pintype "bidirectional+no_connect"))
    )
    (net (code "73") (name "unconnected-(U2A-PJ1-Pad117)") (class "Default")
      (node (ref "U2") (pin "117") (pinfunction "PJ1_117") (pintype "bidirectional+no_connect"))
    )
    (net (code "74") (name "unconnected-(U2A-PK0-Pad18)") (class "Default")
      (node (ref "U2") (pin "18") (pinfunction "PK0_18") (pintype "bidirectional+no_connect"))
    )
    (net (code "75") (name "unconnected-(U2A-PK1-Pad19)") (class "Default")
      (node (ref "U2") (pin "19") (pinfunction "PK1_19") (pintype "bidirectional+no_connect"))
    )
    (net (code "76") (name "unconnected-(U2A-PK2-Pad20)") (class "Default")
      (node (ref "U2") (pin "20") (pinfunction "PK2_20") (pintype "bidirectional+no_connect"))
    )
    (net (code "77") (name "unconnected-(U2A-PK3-Pad21)") (class "Default")
      (node (ref "U2") (pin "21") (pinfunction "PK3_21") (pintype "bidirectional+no_connect"))
    )
    (net (code "78") (name "unconnected-(U2B-PL0-Pad81)") (class "Default")
      (node (ref "U2") (pin "81") (pinfunction "PL0_81") (pintype "bidirectional+no_connect"))
    )
    (net (code "79") (name "unconnected-(U2B-PL1-Pad82)") (class "Default")
      (node (ref "U2") (pin "82") (pinfunction "PL1_82") (pintype "bidirectional+no_connect"))
    )
    (net (code "80") (name "unconnected-(U2B-PL2-Pad83)") (class "Default")
      (node (ref "U2") (pin "83") (pinfunction "PL2_83") (pintype "bidirectional+no_connect"))
    )
    (net (code "81") (name "unconnected-(U2B-PL3-Pad84)") (class "Default")
      (node (ref "U2") (pin "84") (pinfunction "PL3_84") (pintype "bidirectional+no_connect"))
    )
    (net (code "82") (name "unconnected-(U2B-PL4-Pad85)") (class "Default")
      (node (ref "U2") (pin "85") (pinfunction "PL4_85") (pintype "bidirectional+no_connect"))
    )
    (net (code "83") (name "unconnected-(U2B-PL5-Pad86)") (class "Default")
      (node (ref "U2") (pin "86") (pinfunction "PL5_86") (pintype "bidirectional+no_connect"))
    )
    (net (code "84") (name "unconnected-(U2B-PM0-Pad78)") (class "Default")
      (node (ref "U2") (pin "78") (pinfunction "PM0_78") (pintype "bidirectional+no_connect"))
    )
    (net (code "85") (name "unconnected-(U2B-PM1-Pad77)") (class "Default")
      (node (ref "U2") (pin "77") (pinfunction "PM1_77") (pintype "bidirectional+no_connect"))
    )
    (net (code "86") (name "unconnected-(U2B-PM2-Pad76)") (class "Default")
      (node (ref "U2") (pin "76") (pinfunction "PM2_76") (pintype "bidirectional+no_connect"))
    )
    (net (code "87") (name "unconnected-(U2B-PM3-Pad75)") (class "Default")
      (node (ref "U2") (pin "75") (pinfunction "PM3_75") (pintype "bidirectional+no_connect"))
    )
    (net (code "88") (name "unconnected-(U2B-PM4-Pad74)") (class "Default")
      (node (ref "U2") (pin "74") (pinfunction "PM4_74") (pintype "bidirectional+no_connect"))
    )
    (net (code "89") (name "unconnected-(U2B-PM5-Pad73)") (class "Default")
      (node (ref "U2") (pin "73") (pinfunction "PM5_73") (pintype "bidirectional+no_connect"))
    )
    (net (code "90") (name "unconnected-(U2B-PM6-Pad72)") (class "Default")
      (node (ref "U2") (pin "72") (pinfunction "PM6_72") (pintype "bidirectional+no_connect"))
    )
    (net (code "91") (name "unconnected-(U2B-PM7-Pad71)") (class "Default")
      (node (ref "U2") (pin "71") (pinfunction "PM7_71") (pintype "bidirectional+no_connect"))
    )
    (net (code "92") (name "unconnected-(U2B-PN0-Pad107)") (class "Default")
      (node (ref "U2") (pin "107") (pinfunction "PN0_107") (pintype "bidirectional+no_connect"))
    )
    (net (code "93") (name "unconnected-(U2B-PN1-Pad108)") (class "Default")
      (node (ref "U2") (pin "108") (pinfunction "PN1_108") (pintype "bidirectional+no_connect"))
    )
    (net (code "94") (name "unconnected-(U2B-PN2-Pad109)") (class "Default")
      (node (ref "U2") (pin "109") (pinfunction "PN2_109") (pintype "bidirectional+no_connect"))
    )
    (net (code "95") (name "unconnected-(U2B-PN3-Pad110)") (class "Default")
      (node (ref "U2") (pin "110") (pinfunction "PN3_110") (pintype "bidirectional+no_connect"))
    )
    (net (code "96") (name "unconnected-(U2B-PN4-Pad111)") (class "Default")
      (node (ref "U2") (pin "111") (pinfunction "PN4_111") (pintype "bidirectional+no_connect"))
    )
    (net (code "97") (name "unconnected-(U2B-PN5-Pad112)") (class "Default")
      (node (ref "U2") (pin "112") (pinfunction "PN5_112") (pintype "bidirectional+no_connect"))
    )
    (net (code "98") (name "unconnected-(U2B-PP0-Pad118)") (class "Default")
      (node (ref "U2") (pin "118") (pinfunction "PP0_118") (pintype "bidirectional+no_connect"))
    )
    (net (code "99") (name "unconnected-(U2B-PP1-Pad119)") (class "Default")
      (node (ref "U2") (pin "119") (pinfunction "PP1_119") (pintype "bidirectional+no_connect"))
    )
    (net (code "100") (name "unconnected-(U2B-PP2-Pad103)") (class "Default")
      (node (ref "U2") (pin "103") (pinfunction "PP2_103") (pintype "bidirectional+no_connect"))
    )
    (net (code "101") (name "unconnected-(U2B-PP3-Pad104)") (class "Default")
      (node (ref "U2") (pin "104") (pinfunction "PP3_104") (pintype "bidirectional+no_connect"))
    )
    (net (code "102") (name "unconnected-(U2B-PP4-Pad105)") (class "Default")
      (node (ref "U2") (pin "105") (pinfunction "PP4_105") (pintype "bidirectional+no_connect"))
    )
    (net (code "103") (name "unconnected-(U2B-PP5-Pad106)") (class "Default")
      (node (ref "U2") (pin "106") (pinfunction "PP5_106") (pintype "bidirectional+no_connect"))
    )
    (net (code "104") (name "unconnected-(U2B-PQ0-Pad5)") (class "Default")
      (node (ref "U2") (pin "5") (pinfunction "PQ0_5") (pintype "bidirectional+no_connect"))
    )
    (net (code "105") (name "unconnected-(U2B-PQ1-Pad6)") (class "Default")
      (node (ref "U2") (pin "6") (pinfunction "PQ1_6") (pintype "bidirectional+no_connect"))
    )
    (net (code "106") (name "unconnected-(U2B-PQ2-Pad11)") (class "Default")
      (node (ref "U2") (pin "11") (pinfunction "PQ2_11") (pintype "bidirectional+no_connect"))
    )
    (net (code "107") (name "unconnected-(U2B-PQ3-Pad27)") (class "Default")
      (node (ref "U2") (pin "27") (pinfunction "PQ3_27") (pintype "bidirectional+no_connect"))
    )
    (net (code "108") (name "unconnected-(U2B-PQ4-Pad102)") (class "Default")
      (node (ref "U2") (pin "102") (pinfunction "PQ4_102") (pintype "bidirectional+no_connect"))
    )
    (net (code "109") (name "unconnected-(U2C-EN0RXIN-Pad53)") (class "Default")
      (node (ref "U2") (pin "53") (pinfunction "EN0RXIN_53") (pintype "bidirectional+no_connect"))
    )
    (net (code "110") (name "unconnected-(U2C-EN0RXIP-Pad54)") (class "Default")
      (node (ref "U2") (pin "54") (pinfunction "EN0RXIP_54") (pintype "bidirectional+no_connect"))
    )
    (net (code "111") (name "unconnected-(U2C-EN0TXON-Pad56)") (class "Default")
      (node (ref "U2") (pin "56") (pinfunction "EN0TXON_56") (pintype "bidirectional+no_connect"))
    )
    (net (code "112") (name "unconnected-(U2C-EN0TXOP-Pad57)") (class "Default")
      (node (ref "U2") (pin "57") (pinfunction "EN0TXOP_57") (pintype "bidirectional+no_connect"))
    )
    (net (code "113") (name "unconnected-(U2C-HIB-Pad65)") (class "Default")
      (node (ref "U2") (pin "65") (pinfunction "HIB_65") (pintype "output+no_connect"))
    )
    (net (code "114") (name "unconnected-(U2C-XOSC1-Pad67)") (class "Default")
      (node (ref "U2") (pin "67") (pinfunction "XOSC1_67") (pintype "output+no_connect"))
    )
    (net (code "115") (name "unconnected-(U12-IO1-Pad1)") (class "Default")
      (node (ref "U12") (pin "1") (pinfunction "IO1_1") (pintype "passive+no_connect"))
    )
  )
)
